# Datalore-IP-M4.net
KiCad netlist of a schematic drawn in EAGLE
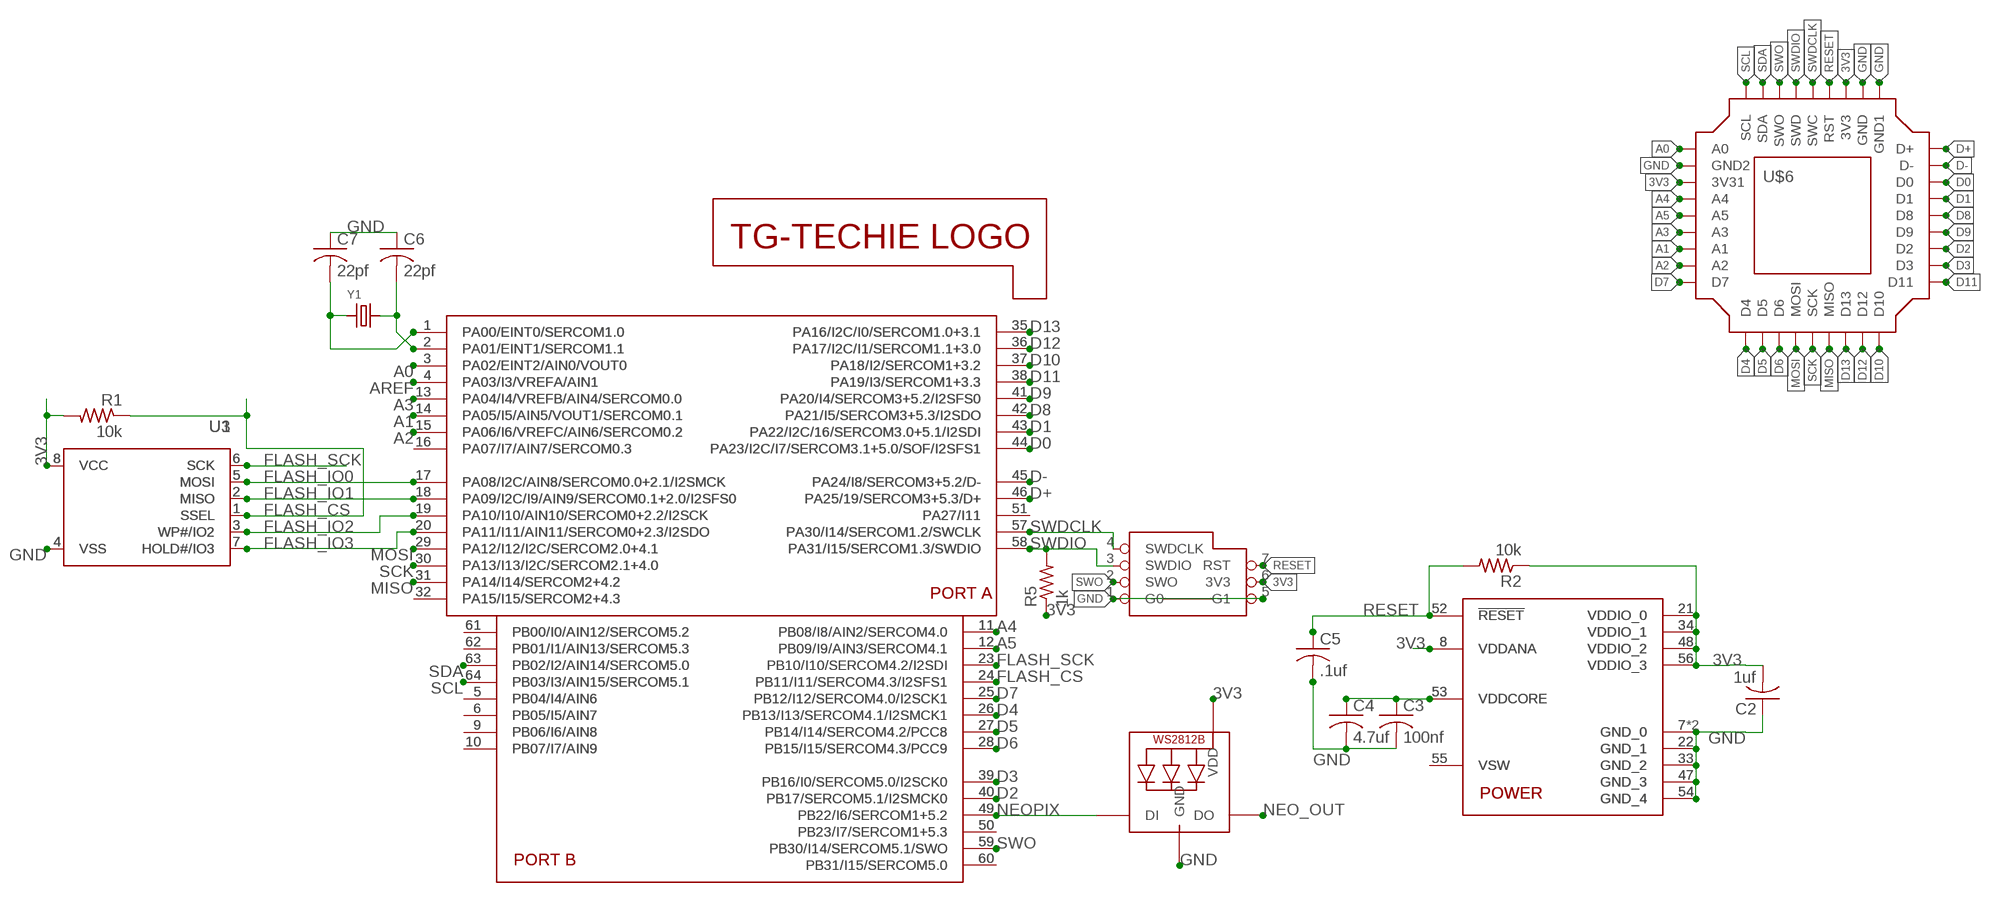
[diagram p0: schematic, sheet 1]

(export (version "E")
  (design (tool "Eeschema 10.0.6"))
  (components
    (comp (ref "C2")
      (value "1uf")
      (footprint "eagle-import:TG-C0805MP")
      (libsource (lib "eagle-import") (part "C-TG"))
    )
    (comp (ref "C3")
      (value "100nf")
      (footprint "eagle-import:TG-C0805MP")
      (libsource (lib "eagle-import") (part "C-TG"))
    )
    (comp (ref "C4")
      (value "4.7uf")
      (footprint "eagle-import:TG-C0805MP")
      (libsource (lib "eagle-import") (part "C-TG"))
    )
    (comp (ref "C5")
      (value ".1uf")
      (footprint "eagle-import:TG-C0805MP")
      (libsource (lib "eagle-import") (part "C-TG"))
    )
    (comp (ref "C6")
      (value "22pf")
      (footprint "eagle-import:TG-C0805MP")
      (libsource (lib "eagle-import") (part "C-TG"))
    )
    (comp (ref "C7")
      (value "22pf")
      (footprint "eagle-import:TG-C0805MP")
      (libsource (lib "eagle-import") (part "C-TG"))
    )
    (comp (ref "LED1")
      (value "LED-NEO-WS2812B3535")
      (footprint "eagle-import:LED3535")
      (libsource (lib "eagle-import") (part "LED-NEO-WS2812B3535"))
    )
    (comp (ref "R1")
      (value "10k")
      (footprint "eagle-import:TG-R0805")
      (libsource (lib "eagle-import") (part "R_TG"))
    )
    (comp (ref "R2")
      (value "10k")
      (footprint "eagle-import:TG-R0805")
      (libsource (lib "eagle-import") (part "R_TG"))
    )
    (comp (ref "R5")
      (value "1k")
      (footprint "eagle-import:TG-R0805")
      (libsource (lib "eagle-import") (part "R_TG"))
    )
    (comp (ref "U$1")
      (value "MCU-ATSAMD51J-ADATQFP")
      (footprint "eagle-import:QFP50P1200X1200X120-64N")
      (libsource (lib "eagle-import") (part "MCU-ATSAMD51J-ADATQFP"))
    )
    (comp (ref "U$2")
      (value "MCU-ATSAMD51J-ADAADA")
      (footprint "eagle-import:MICROBUILDER_PQFN64-1")
      (libsource (lib "eagle-import") (part "0TG-Lib v01.4_MCU-ATSAMD51J-ADAADA"))
    )
    (comp (ref "U$4")
      (value "SWD_POGO")
      (footprint "eagle-import:SWD_POGO")
      (libsource (lib "eagle-import") (part "SWD_POGO"))
    )
    (comp (ref "U$5")
      (value "LOGO-TG_TECHIEBIG?")
      (footprint "eagle-import:LOGO_TG_TEST_LARGE")
      (libsource (lib "eagle-import") (part "LOGO-TG_TECHIEBIG?"))
    )
    (comp (ref "U$6")
      (value "DATALORE-IP-M4_PKG")
      (footprint "eagle-import:DL_IP_36-.1IN-PACKAGE")
      (libsource (lib "eagle-import") (part "DATALORE-IP-M4_PKG"))
    )
    (comp (ref "U1")
      (value "FLASH-SPI-SOIC8")
      (footprint "eagle-import:SOIC8_150MIL")
      (libsource (lib "eagle-import") (part "FLASH-SPI-SOIC8"))
    )
    (comp (ref "U3")
      (value "FLASH-SPI-SOIC8208MIL")
      (footprint "eagle-import:SOIC8_208MIL")
      (libsource (lib "eagle-import") (part "FLASH-SPI-SOIC8208MIL"))
    )
    (comp (ref "Y1")
      (value "XTAL_ADA4.9X1.8")
      (footprint "eagle-import:MICROBUILDER_CRYSTAL_4.9X1.8")
      (libsource (lib "eagle-import") (part "XTAL_ADA4.9X1.8"))
    )
  )
  (nets
    (net (code "1") (name "/AREF") (class "Default")
      (node (ref "U$1") (pin "4") (pinfunction "PA03/I3/VREFA/AIN1_4") (pintype "bidirectional"))
      (node (ref "U$2") (pin "4") (pinfunction "PA03/I3/VREFA/AIN1_4") (pintype "bidirectional"))
    )
    (net (code "2") (name "/FLASH_CS") (class "Default")
      (node (ref "R1") (pin "1") (pinfunction "1_1") (pintype "passive"))
      (node (ref "U$1") (pin "24") (pinfunction "PB11/I11/SERCOM4.3/I2SFS1_24") (pintype "bidirectional"))
      (node (ref "U$2") (pin "24") (pinfunction "PB11/I11/SERCOM4.3/I2SFS1_24") (pintype "bidirectional"))
      (node (ref "U1") (pin "1") (pinfunction "SSEL_1") (pintype "bidirectional"))
      (node (ref "U3") (pin "1") (pinfunction "SSEL_1") (pintype "bidirectional"))
    )
    (net (code "3") (name "/FLASH_IO0") (class "Default")
      (node (ref "U$1") (pin "17") (pinfunction "PA08/I2C/AIN8/SERCOM0.0+2.1/I2SMCK_17") (pintype "bidirectional"))
      (node (ref "U$2") (pin "17") (pinfunction "PA08/I2C/AIN8/SERCOM0.0+2.1/I2SMCK_17") (pintype "bidirectional"))
      (node (ref "U1") (pin "5") (pinfunction "MOSI_5") (pintype "bidirectional"))
      (node (ref "U3") (pin "5") (pinfunction "MOSI_5") (pintype "bidirectional"))
    )
    (net (code "4") (name "/FLASH_IO1") (class "Default")
      (node (ref "U$1") (pin "18") (pinfunction "PA09/I2C/I9/AIN9/SERCOM0.1+2.0/I2SFS0_18") (pintype "bidirectional"))
      (node (ref "U$2") (pin "18") (pinfunction "PA09/I2C/I9/AIN9/SERCOM0.1+2.0/I2SFS0_18") (pintype "bidirectional"))
      (node (ref "U1") (pin "2") (pinfunction "MISO_2") (pintype "bidirectional"))
      (node (ref "U3") (pin "2") (pinfunction "MISO_2") (pintype "bidirectional"))
    )
    (net (code "5") (name "/FLASH_IO2") (class "Default")
      (node (ref "U$1") (pin "19") (pinfunction "PA10/I10/AIN10/SERCOM0+2.2/I2SCK_19") (pintype "bidirectional"))
      (node (ref "U$2") (pin "19") (pinfunction "PA10/I10/AIN10/SERCOM0+2.2/I2SCK_19") (pintype "bidirectional"))
      (node (ref "U1") (pin "3") (pinfunction "WP#/IO2_3") (pintype "bidirectional"))
      (node (ref "U3") (pin "3") (pinfunction "WP#/IO2_3") (pintype "bidirectional"))
    )
    (net (code "6") (name "/FLASH_IO3") (class "Default")
      (node (ref "U$1") (pin "20") (pinfunction "PA11/I11/AIN11/SERCOM0+2.3/I2SDO_20") (pintype "bidirectional"))
      (node (ref "U$2") (pin "20") (pinfunction "PA11/I11/AIN11/SERCOM0+2.3/I2SDO_20") (pintype "bidirectional"))
      (node (ref "U1") (pin "7") (pinfunction "HOLD#/IO3_7") (pintype "bidirectional"))
      (node (ref "U3") (pin "7") (pinfunction "HOLD#/IO3_7") (pintype "bidirectional"))
    )
    (net (code "7") (name "/FLASH_SCK") (class "Default")
      (node (ref "U$1") (pin "23") (pinfunction "PB10/I10/SERCOM4.2/I2SDI_23") (pintype "bidirectional"))
      (node (ref "U$2") (pin "23") (pinfunction "PB10/I10/SERCOM4.2/I2SDI_23") (pintype "bidirectional"))
      (node (ref "U1") (pin "6") (pinfunction "SCK_6") (pintype "bidirectional"))
      (node (ref "U3") (pin "6") (pinfunction "SCK_6") (pintype "bidirectional"))
    )
    (net (code "8") (name "/NEOPIX") (class "Default")
      (node (ref "LED1") (pin "1") (pinfunction "DI_1") (pintype "input"))
      (node (ref "U$1") (pin "49") (pinfunction "PB22/I6/SERCOM1+5.2_49") (pintype "bidirectional"))
      (node (ref "U$2") (pin "49") (pinfunction "PB22/I6/SERCOM1+5.2_49") (pintype "bidirectional"))
    )
    (net (code "9") (name "/NEO_OUT") (class "Default")
      (node (ref "LED1") (pin "3") (pinfunction "DO_3") (pintype "output"))
    )
    (net (code "10") (name "3V3") (class "Default")
      (node (ref "C2") (pin "2") (pinfunction "2_2") (pintype "passive"))
      (node (ref "LED1") (pin "2") (pinfunction "VDD_2") (pintype "power_in"))
      (node (ref "R1") (pin "2") (pinfunction "2_2") (pintype "passive"))
      (node (ref "R2") (pin "1") (pinfunction "1_1") (pintype "passive"))
      (node (ref "R5") (pin "1") (pinfunction "1_1") (pintype "passive"))
      (node (ref "U$1") (pin "21") (pinfunction "VDDIO_0_21") (pintype "bidirectional"))
      (node (ref "U$1") (pin "34") (pinfunction "VDDIO_1_34") (pintype "bidirectional"))
      (node (ref "U$1") (pin "48") (pinfunction "VDDIO_2_48") (pintype "bidirectional"))
      (node (ref "U$1") (pin "56") (pinfunction "VDDIO_3_56") (pintype "bidirectional"))
      (node (ref "U$1") (pin "8") (pinfunction "VDDANA_8") (pintype "bidirectional"))
      (node (ref "U$2") (pin "21") (pinfunction "VDDIO_0_21") (pintype "bidirectional"))
      (node (ref "U$2") (pin "34") (pinfunction "VDDIO_1_34") (pintype "bidirectional"))
      (node (ref "U$2") (pin "48") (pinfunction "VDDIO_2_48") (pintype "bidirectional"))
      (node (ref "U$2") (pin "56") (pinfunction "VDDIO_3_56") (pintype "bidirectional"))
      (node (ref "U$2") (pin "8") (pinfunction "VDDANA_8") (pintype "bidirectional"))
      (node (ref "U$4") (pin "6") (pinfunction "3V3_6") (pintype "bidirectional"))
      (node (ref "U$6") (pin "34") (pinfunction "3V31_34") (pintype "bidirectional"))
      (node (ref "U$6") (pin "7") (pinfunction "3V3_7") (pintype "bidirectional"))
      (node (ref "U1") (pin "8") (pinfunction "VCC_8") (pintype "bidirectional"))
      (node (ref "U3") (pin "8") (pinfunction "VCC_8") (pintype "bidirectional"))
    )
    (net (code "11") (name "A0") (class "Default")
      (node (ref "U$1") (pin "3") (pinfunction "PA02/EINT2/AIN0/VOUT0_3") (pintype "bidirectional"))
      (node (ref "U$2") (pin "3") (pinfunction "PA02/EINT2/AIN0/VOUT0_3") (pintype "bidirectional"))
      (node (ref "U$6") (pin "36") (pinfunction "A0_36") (pintype "bidirectional"))
    )
    (net (code "12") (name "A1") (class "Default")
      (node (ref "U$1") (pin "14") (pinfunction "PA05/I5/AIN5/VOUT1/SERCOM0.1_14") (pintype "bidirectional"))
      (node (ref "U$2") (pin "14") (pinfunction "PA05/I5/AIN5/VOUT1/SERCOM0.1_14") (pintype "bidirectional"))
      (node (ref "U$6") (pin "30") (pinfunction "A1_30") (pintype "bidirectional"))
    )
    (net (code "13") (name "A2") (class "Default")
      (node (ref "U$1") (pin "15") (pinfunction "PA06/I6/VREFC/AIN6/SERCOM0.2_15") (pintype "bidirectional"))
      (node (ref "U$2") (pin "15") (pinfunction "PA06/I6/VREFC/AIN6/SERCOM0.2_15") (pintype "bidirectional"))
      (node (ref "U$6") (pin "29") (pinfunction "A2_29") (pintype "bidirectional"))
    )
    (net (code "14") (name "A3") (class "Default")
      (node (ref "U$1") (pin "13") (pinfunction "PA04/I4/VREFB/AIN4/SERCOM0.0_13") (pintype "bidirectional"))
      (node (ref "U$2") (pin "13") (pinfunction "PA04/I4/VREFB/AIN4/SERCOM0.0_13") (pintype "bidirectional"))
      (node (ref "U$6") (pin "31") (pinfunction "A3_31") (pintype "bidirectional"))
    )
    (net (code "15") (name "A4") (class "Default")
      (node (ref "U$1") (pin "11") (pinfunction "PB08/I8/AIN2/SERCOM4.0_11") (pintype "bidirectional"))
      (node (ref "U$2") (pin "11") (pinfunction "PB08/I8/AIN2/SERCOM4.0_11") (pintype "bidirectional"))
      (node (ref "U$6") (pin "33") (pinfunction "A4_33") (pintype "bidirectional"))
    )
    (net (code "16") (name "A5") (class "Default")
      (node (ref "U$1") (pin "12") (pinfunction "PB09/I9/AIN3/SERCOM4.1_12") (pintype "bidirectional"))
      (node (ref "U$2") (pin "12") (pinfunction "PB09/I9/AIN3/SERCOM4.1_12") (pintype "bidirectional"))
      (node (ref "U$6") (pin "32") (pinfunction "A5_32") (pintype "bidirectional"))
    )
    (net (code "17") (name "D+") (class "Default")
      (node (ref "U$1") (pin "46") (pinfunction "PA25/19/SERCOM3+5.3/D+_46") (pintype "bidirectional"))
      (node (ref "U$2") (pin "46") (pinfunction "PA25/19/SERCOM3+5.3/D+_46") (pintype "bidirectional"))
      (node (ref "U$6") (pin "10") (pinfunction "D+_10") (pintype "bidirectional"))
    )
    (net (code "18") (name "D-") (class "Default")
      (node (ref "U$1") (pin "45") (pinfunction "PA24/I8/SERCOM3+5.2/D-_45") (pintype "bidirectional"))
      (node (ref "U$2") (pin "45") (pinfunction "PA24/I8/SERCOM3+5.2/D-_45") (pintype "bidirectional"))
      (node (ref "U$6") (pin "11") (pinfunction "D-_11") (pintype "bidirectional"))
    )
    (net (code "19") (name "D0") (class "Default")
      (node (ref "U$1") (pin "44") (pinfunction "PA23/I2C/I7/SERCOM3.1+5.0/SOF/I2SFS1_44") (pintype "bidirectional"))
      (node (ref "U$2") (pin "44") (pinfunction "PA23/I2C/I7/SERCOM3.1+5.0/SOF/I2SFS1_44") (pintype "bidirectional"))
      (node (ref "U$6") (pin "12") (pinfunction "D0_12") (pintype "bidirectional"))
    )
    (net (code "20") (name "D1") (class "Default")
      (node (ref "U$1") (pin "43") (pinfunction "PA22/I2C/16/SERCOM3.0+5.1/I2SDI_43") (pintype "bidirectional"))
      (node (ref "U$2") (pin "43") (pinfunction "PA22/I2C/16/SERCOM3.0+5.1/I2SDI_43") (pintype "bidirectional"))
      (node (ref "U$6") (pin "13") (pinfunction "D1_13") (pintype "bidirectional"))
    )
    (net (code "21") (name "D2") (class "Default")
      (node (ref "U$1") (pin "40") (pinfunction "PB17/SERCOM5.1/I2SMCK0_40") (pintype "bidirectional"))
      (node (ref "U$2") (pin "40") (pinfunction "PB17/SERCOM5.1/I2SMCK0_40") (pintype "bidirectional"))
      (node (ref "U$6") (pin "16") (pinfunction "D2_16") (pintype "bidirectional"))
    )
    (net (code "22") (name "D3") (class "Default")
      (node (ref "U$1") (pin "39") (pinfunction "PB16/I0/SERCOM5.0/I2SCK0_39") (pintype "bidirectional"))
      (node (ref "U$2") (pin "39") (pinfunction "PB16/I0/SERCOM5.0/I2SCK0_39") (pintype "bidirectional"))
      (node (ref "U$6") (pin "17") (pinfunction "D3_17") (pintype "bidirectional"))
    )
    (net (code "23") (name "D4") (class "Default")
      (node (ref "U$1") (pin "26") (pinfunction "PB13/I13/SERCOM4.1/I2SMCK1_26") (pintype "bidirectional"))
      (node (ref "U$2") (pin "26") (pinfunction "PB13/I13/SERCOM4.1/I2SMCK1_26") (pintype "bidirectional"))
      (node (ref "U$6") (pin "27") (pinfunction "D4_27") (pintype "bidirectional"))
    )
    (net (code "24") (name "D5") (class "Default")
      (node (ref "U$1") (pin "27") (pinfunction "PB14/I14/SERCOM4.2/PCC8_27") (pintype "bidirectional"))
      (node (ref "U$2") (pin "27") (pinfunction "PB14/I14/SERCOM4.2/PCC8_27") (pintype "bidirectional"))
      (node (ref "U$6") (pin "26") (pinfunction "D5_26") (pintype "bidirectional"))
    )
    (net (code "25") (name "D6") (class "Default")
      (node (ref "U$1") (pin "28") (pinfunction "PB15/I15/SERCOM4.3/PCC9_28") (pintype "bidirectional"))
      (node (ref "U$2") (pin "28") (pinfunction "PB15/I15/SERCOM4.3/PCC9_28") (pintype "bidirectional"))
      (node (ref "U$6") (pin "25") (pinfunction "D6_25") (pintype "bidirectional"))
    )
    (net (code "26") (name "D7") (class "Default")
      (node (ref "U$1") (pin "25") (pinfunction "PB12/I12/SERCOM4.0/I2SCK1_25") (pintype "bidirectional"))
      (node (ref "U$2") (pin "25") (pinfunction "PB12/I12/SERCOM4.0/I2SCK1_25") (pintype "bidirectional"))
      (node (ref "U$6") (pin "28") (pinfunction "D7_28") (pintype "bidirectional"))
    )
    (net (code "27") (name "D8") (class "Default")
      (node (ref "U$1") (pin "42") (pinfunction "PA21/I5/SERCOM3+5.3/I2SDO_42") (pintype "bidirectional"))
      (node (ref "U$2") (pin "42") (pinfunction "PA21/I5/SERCOM3+5.3/I2SDO_42") (pintype "bidirectional"))
      (node (ref "U$6") (pin "14") (pinfunction "D8_14") (pintype "bidirectional"))
    )
    (net (code "28") (name "D9") (class "Default")
      (node (ref "U$1") (pin "41") (pinfunction "PA20/I4/SERCOM3+5.2/I2SFS0_41") (pintype "bidirectional"))
      (node (ref "U$2") (pin "41") (pinfunction "PA20/I4/SERCOM3+5.2/I2SFS0_41") (pintype "bidirectional"))
      (node (ref "U$6") (pin "15") (pinfunction "D9_15") (pintype "bidirectional"))
    )
    (net (code "29") (name "D10") (class "Default")
      (node (ref "U$1") (pin "37") (pinfunction "PA18/I2/SERCOM1+3.2_37") (pintype "bidirectional"))
      (node (ref "U$2") (pin "37") (pinfunction "PA18/I2/SERCOM1+3.2_37") (pintype "bidirectional"))
      (node (ref "U$6") (pin "19") (pinfunction "D10_19") (pintype "bidirectional"))
    )
    (net (code "30") (name "D11") (class "Default")
      (node (ref "U$1") (pin "38") (pinfunction "PA19/I3/SERCOM1+3.3_38") (pintype "bidirectional"))
      (node (ref "U$2") (pin "38") (pinfunction "PA19/I3/SERCOM1+3.3_38") (pintype "bidirectional"))
      (node (ref "U$6") (pin "18") (pinfunction "D11_18") (pintype "bidirectional"))
    )
    (net (code "31") (name "D12") (class "Default")
      (node (ref "U$1") (pin "36") (pinfunction "PA17/I2C/I1/SERCOM1.1+3.0_36") (pintype "bidirectional"))
      (node (ref "U$2") (pin "36") (pinfunction "PA17/I2C/I1/SERCOM1.1+3.0_36") (pintype "bidirectional"))
      (node (ref "U$6") (pin "20") (pinfunction "D12_20") (pintype "bidirectional"))
    )
    (net (code "32") (name "D13") (class "Default")
      (node (ref "U$1") (pin "35") (pinfunction "PA16/I2C/I0/SERCOM1.0+3.1_35") (pintype "bidirectional"))
      (node (ref "U$2") (pin "35") (pinfunction "PA16/I2C/I0/SERCOM1.0+3.1_35") (pintype "bidirectional"))
      (node (ref "U$6") (pin "21") (pinfunction "D13_21") (pintype "bidirectional"))
    )
    (net (code "33") (name "GND") (class "Default")
      (node (ref "C2") (pin "1") (pinfunction "1_1") (pintype "passive"))
      (node (ref "C3") (pin "2") (pinfunction "2_2") (pintype "passive"))
      (node (ref "C4") (pin "2") (pinfunction "2_2") (pintype "passive"))
      (node (ref "C5") (pin "2") (pinfunction "2_2") (pintype "passive"))
      (node (ref "C6") (pin "1") (pinfunction "1_1") (pintype "passive"))
      (node (ref "C7") (pin "1") (pinfunction "1_1") (pintype "passive"))
      (node (ref "LED1") (pin "4") (pinfunction "GND_4") (pintype "power_in"))
      (node (ref "U$1") (pin "22") (pinfunction "GND_1_22") (pintype "bidirectional"))
      (node (ref "U$1") (pin "33") (pinfunction "GND_2_33") (pintype "bidirectional"))
      (node (ref "U$1") (pin "47") (pinfunction "GND_3_47") (pintype "bidirectional"))
      (node (ref "U$1") (pin "54") (pinfunction "GND_4_54") (pintype "bidirectional"))
      (node (ref "U$1") (pin "7") (pinfunction "GND_0_7") (pintype "bidirectional"))
      (node (ref "U$2") (pin "22") (pinfunction "GND_1_22") (pintype "bidirectional"))
      (node (ref "U$2") (pin "33") (pinfunction "GND_2_33") (pintype "bidirectional"))
      (node (ref "U$2") (pin "47") (pinfunction "GND_3_47") (pintype "bidirectional"))
      (node (ref "U$2") (pin "54") (pinfunction "GND_4_54") (pintype "bidirectional"))
      (node (ref "U$2") (pin "7") (pinfunction "GND_0_7") (pintype "bidirectional"))
      (node (ref "U$2") (pin "EXP") (pinfunction "GND_0_EXP") (pintype "bidirectional"))
      (node (ref "U$4") (pin "1") (pinfunction "G0_1") (pintype "bidirectional"))
      (node (ref "U$4") (pin "5") (pinfunction "G1_5") (pintype "bidirectional"))
      (node (ref "U$6") (pin "35") (pinfunction "GND2_35") (pintype "bidirectional"))
      (node (ref "U$6") (pin "8") (pinfunction "GND_8") (pintype "bidirectional"))
      (node (ref "U$6") (pin "9") (pinfunction "GND1_9") (pintype "bidirectional"))
      (node (ref "U1") (pin "4") (pinfunction "VSS_4") (pintype "bidirectional"))
      (node (ref "U3") (pin "4") (pinfunction "VSS_4") (pintype "bidirectional"))
    )
    (net (code "34") (name "MISO") (class "Default")
      (node (ref "U$1") (pin "31") (pinfunction "PA14/I14/SERCOM2+4.2_31") (pintype "bidirectional"))
      (node (ref "U$2") (pin "31") (pinfunction "PA14/I14/SERCOM2+4.2_31") (pintype "bidirectional"))
      (node (ref "U$6") (pin "22") (pinfunction "MISO_22") (pintype "bidirectional"))
    )
    (net (code "35") (name "MOSI") (class "Default")
      (node (ref "U$1") (pin "29") (pinfunction "PA12/I12/I2C/SERCOM2.0+4.1_29") (pintype "bidirectional"))
      (node (ref "U$2") (pin "29") (pinfunction "PA12/I12/I2C/SERCOM2.0+4.1_29") (pintype "bidirectional"))
      (node (ref "U$6") (pin "24") (pinfunction "MOSI_24") (pintype "bidirectional"))
    )
    (net (code "36") (name "Net-(U$1A-PA00{slash}EINT0{slash}SERCOM1.0)") (class "Default")
      (node (ref "C7") (pin "2") (pinfunction "2_2") (pintype "passive"))
      (node (ref "U$1") (pin "1") (pinfunction "PA00/EINT0/SERCOM1.0_1") (pintype "bidirectional"))
      (node (ref "U$2") (pin "1") (pinfunction "PA00/EINT0/SERCOM1.0_1") (pintype "bidirectional"))
      (node (ref "Y1") (pin "1") (pinfunction "1_1") (pintype "passive"))
    )
    (net (code "37") (name "Net-(U$1A-PA01{slash}EINT1{slash}SERCOM1.1)") (class "Default")
      (node (ref "C6") (pin "2") (pinfunction "2_2") (pintype "passive"))
      (node (ref "U$1") (pin "2") (pinfunction "PA01/EINT1/SERCOM1.1_2") (pintype "bidirectional"))
      (node (ref "U$2") (pin "2") (pinfunction "PA01/EINT1/SERCOM1.1_2") (pintype "bidirectional"))
      (node (ref "Y1") (pin "2") (pinfunction "2_2") (pintype "passive"))
    )
    (net (code "38") (name "Net-(U$1A-PA07{slash}I7{slash}AIN7{slash}SERCOM0.3)") (class "Default")
      (node (ref "U$1") (pin "16") (pinfunction "PA07/I7/AIN7/SERCOM0.3_16") (pintype "bidirectional"))
      (node (ref "U$2") (pin "16") (pinfunction "PA07/I7/AIN7/SERCOM0.3_16") (pintype "bidirectional"))
    )
    (net (code "39") (name "Net-(U$1A-PA15{slash}I15{slash}SERCOM2+4.3)") (class "Default")
      (node (ref "U$1") (pin "32") (pinfunction "PA15/I15/SERCOM2+4.3_32") (pintype "bidirectional"))
      (node (ref "U$2") (pin "32") (pinfunction "PA15/I15/SERCOM2+4.3_32") (pintype "bidirectional"))
    )
    (net (code "40") (name "Net-(U$1A-PA27{slash}I11)") (class "Default")
      (node (ref "U$1") (pin "51") (pinfunction "PA27/I11_51") (pintype "bidirectional"))
      (node (ref "U$2") (pin "51") (pinfunction "PA27/I11_51") (pintype "bidirectional"))
    )
    (net (code "41") (name "Net-(U$1B-PB00{slash}I0{slash}AIN12{slash}SERCOM5.2)") (class "Default")
      (node (ref "U$1") (pin "61") (pinfunction "PB00/I0/AIN12/SERCOM5.2_61") (pintype "bidirectional"))
      (node (ref "U$2") (pin "61") (pinfunction "PB00/I0/AIN12/SERCOM5.2_61") (pintype "bidirectional"))
    )
    (net (code "42") (name "Net-(U$1B-PB01{slash}I1{slash}AIN13{slash}SERCOM5.3)") (class "Default")
      (node (ref "U$1") (pin "62") (pinfunction "PB01/I1/AIN13/SERCOM5.3_62") (pintype "bidirectional"))
      (node (ref "U$2") (pin "62") (pinfunction "PB01/I1/AIN13/SERCOM5.3_62") (pintype "bidirectional"))
    )
    (net (code "43") (name "Net-(U$1B-PB04{slash}I4{slash}AIN6)") (class "Default")
      (node (ref "U$1") (pin "5") (pinfunction "PB04/I4/AIN6_5") (pintype "bidirectional"))
      (node (ref "U$2") (pin "5") (pinfunction "PB04/I4/AIN6_5") (pintype "bidirectional"))
    )
    (net (code "44") (name "Net-(U$1B-PB05{slash}I5{slash}AIN7)") (class "Default")
      (node (ref "U$1") (pin "6") (pinfunction "PB05/I5/AIN7_6") (pintype "bidirectional"))
      (node (ref "U$2") (pin "6") (pinfunction "PB05/I5/AIN7_6") (pintype "bidirectional"))
    )
    (net (code "45") (name "Net-(U$1B-PB06{slash}I6{slash}AIN8)") (class "Default")
      (node (ref "U$1") (pin "9") (pinfunction "PB06/I6/AIN8_9") (pintype "bidirectional"))
      (node (ref "U$2") (pin "9") (pinfunction "PB06/I6/AIN8_9") (pintype "bidirectional"))
    )
    (net (code "46") (name "Net-(U$1B-PB07{slash}I7{slash}AIN9)") (class "Default")
      (node (ref "U$1") (pin "10") (pinfunction "PB07/I7/AIN9_10") (pintype "bidirectional"))
      (node (ref "U$2") (pin "10") (pinfunction "PB07/I7/AIN9_10") (pintype "bidirectional"))
    )
    (net (code "47") (name "Net-(U$1B-PB23{slash}I7{slash}SERCOM1+5.3)") (class "Default")
      (node (ref "U$1") (pin "50") (pinfunction "PB23/I7/SERCOM1+5.3_50") (pintype "bidirectional"))
      (node (ref "U$2") (pin "50") (pinfunction "PB23/I7/SERCOM1+5.3_50") (pintype "bidirectional"))
    )
    (net (code "48") (name "Net-(U$1B-PB31{slash}I15{slash}SERCOM5.0)") (class "Default")
      (node (ref "U$1") (pin "60") (pinfunction "PB31/I15/SERCOM5.0_60") (pintype "bidirectional"))
      (node (ref "U$2") (pin "60") (pinfunction "PB31/I15/SERCOM5.0_60") (pintype "bidirectional"))
    )
    (net (code "49") (name "Net-(U$1C-VDDCORE)") (class "Default")
      (node (ref "C3") (pin "1") (pinfunction "1_1") (pintype "passive"))
      (node (ref "C4") (pin "1") (pinfunction "1_1") (pintype "passive"))
      (node (ref "U$1") (pin "53") (pinfunction "VDDCORE_53") (pintype "bidirectional"))
      (node (ref "U$2") (pin "53") (pinfunction "VDDCORE_53") (pintype "bidirectional"))
    )
    (net (code "50") (name "Net-(U$1C-VSW)") (class "Default")
      (node (ref "U$1") (pin "55") (pinfunction "VSW_55") (pintype "bidirectional"))
      (node (ref "U$2") (pin "55") (pinfunction "VSW_55") (pintype "bidirectional"))
    )
    (net (code "51") (name "RESET") (class "Default")
      (node (ref "C5") (pin "1") (pinfunction "1_1") (pintype "passive"))
      (node (ref "R2") (pin "2") (pinfunction "2_2") (pintype "passive"))
      (node (ref "U$1") (pin "52") (pinfunction "~{RESET}_52") (pintype "bidirectional"))
      (node (ref "U$2") (pin "52") (pinfunction "~{RESET}_52") (pintype "bidirectional"))
      (node (ref "U$4") (pin "7") (pinfunction "RST_7") (pintype "bidirectional"))
      (node (ref "U$6") (pin "6") (pinfunction "RST_6") (pintype "bidirectional"))
    )
    (net (code "52") (name "SCK") (class "Default")
      (node (ref "U$1") (pin "30") (pinfunction "PA13/I13/I2C/SERCOM2.1+4.0_30") (pintype "bidirectional"))
      (node (ref "U$2") (pin "30") (pinfunction "PA13/I13/I2C/SERCOM2.1+4.0_30") (pintype "bidirectional"))
      (node (ref "U$6") (pin "23") (pinfunction "SCK_23") (pintype "bidirectional"))
    )
    (net (code "53") (name "SCL") (class "Default")
      (node (ref "U$1") (pin "64") (pinfunction "PB03/I3/AIN15/SERCOM5.1_64") (pintype "bidirectional"))
      (node (ref "U$2") (pin "64") (pinfunction "PB03/I3/AIN15/SERCOM5.1_64") (pintype "bidirectional"))
      (node (ref "U$6") (pin "1") (pinfunction "SCL_1") (pintype "bidirectional"))
    )
    (net (code "54") (name "SDA") (class "Default")
      (node (ref "U$1") (pin "63") (pinfunction "PB02/I2/AIN14/SERCOM5.0_63") (pintype "bidirectional"))
      (node (ref "U$2") (pin "63") (pinfunction "PB02/I2/AIN14/SERCOM5.0_63") (pintype "bidirectional"))
      (node (ref "U$6") (pin "2") (pinfunction "SDA_2") (pintype "bidirectional"))
    )
    (net (code "55") (name "SWDCLK") (class "Default")
      (node (ref "U$1") (pin "57") (pinfunction "PA30/I14/SERCOM1.2/SWCLK_57") (pintype "bidirectional"))
      (node (ref "U$2") (pin "57") (pinfunction "PA30/I14/SERCOM1.2/SWCLK_57") (pintype "bidirectional"))
      (node (ref "U$4") (pin "4") (pinfunction "SWDCLK_4") (pintype "bidirectional"))
      (node (ref "U$6") (pin "5") (pinfunction "SWC_5") (pintype "bidirectional"))
    )
    (net (code "56") (name "SWDIO") (class "Default")
      (node (ref "R5") (pin "2") (pinfunction "2_2") (pintype "passive"))
      (node (ref "U$1") (pin "58") (pinfunction "PA31/I15/SERCOM1.3/SWDIO_58") (pintype "bidirectional"))
      (node (ref "U$2") (pin "58") (pinfunction "PA31/I15/SERCOM1.3/SWDIO_58") (pintype "bidirectional"))
      (node (ref "U$4") (pin "3") (pinfunction "SWDIO_3") (pintype "bidirectional"))
      (node (ref "U$6") (pin "4") (pinfunction "SWD_4") (pintype "bidirectional"))
    )
    (net (code "57") (name "SWO") (class "Default")
      (node (ref "U$1") (pin "59") (pinfunction "PB30/I14/SERCOM5.1/SWO_59") (pintype "bidirectional"))
      (node (ref "U$2") (pin "59") (pinfunction "PB30/I14/SERCOM5.1/SWO_59") (pintype "bidirectional"))
      (node (ref "U$4") (pin "2") (pinfunction "SWO_2") (pintype "bidirectional"))
      (node (ref "U$6") (pin "3") (pinfunction "SWO_3") (pintype "bidirectional"))
    )
  )
)
